# ProProject___2024-04-14.net
KiCad netlist of a schematic drawn in EasyEDA Pro
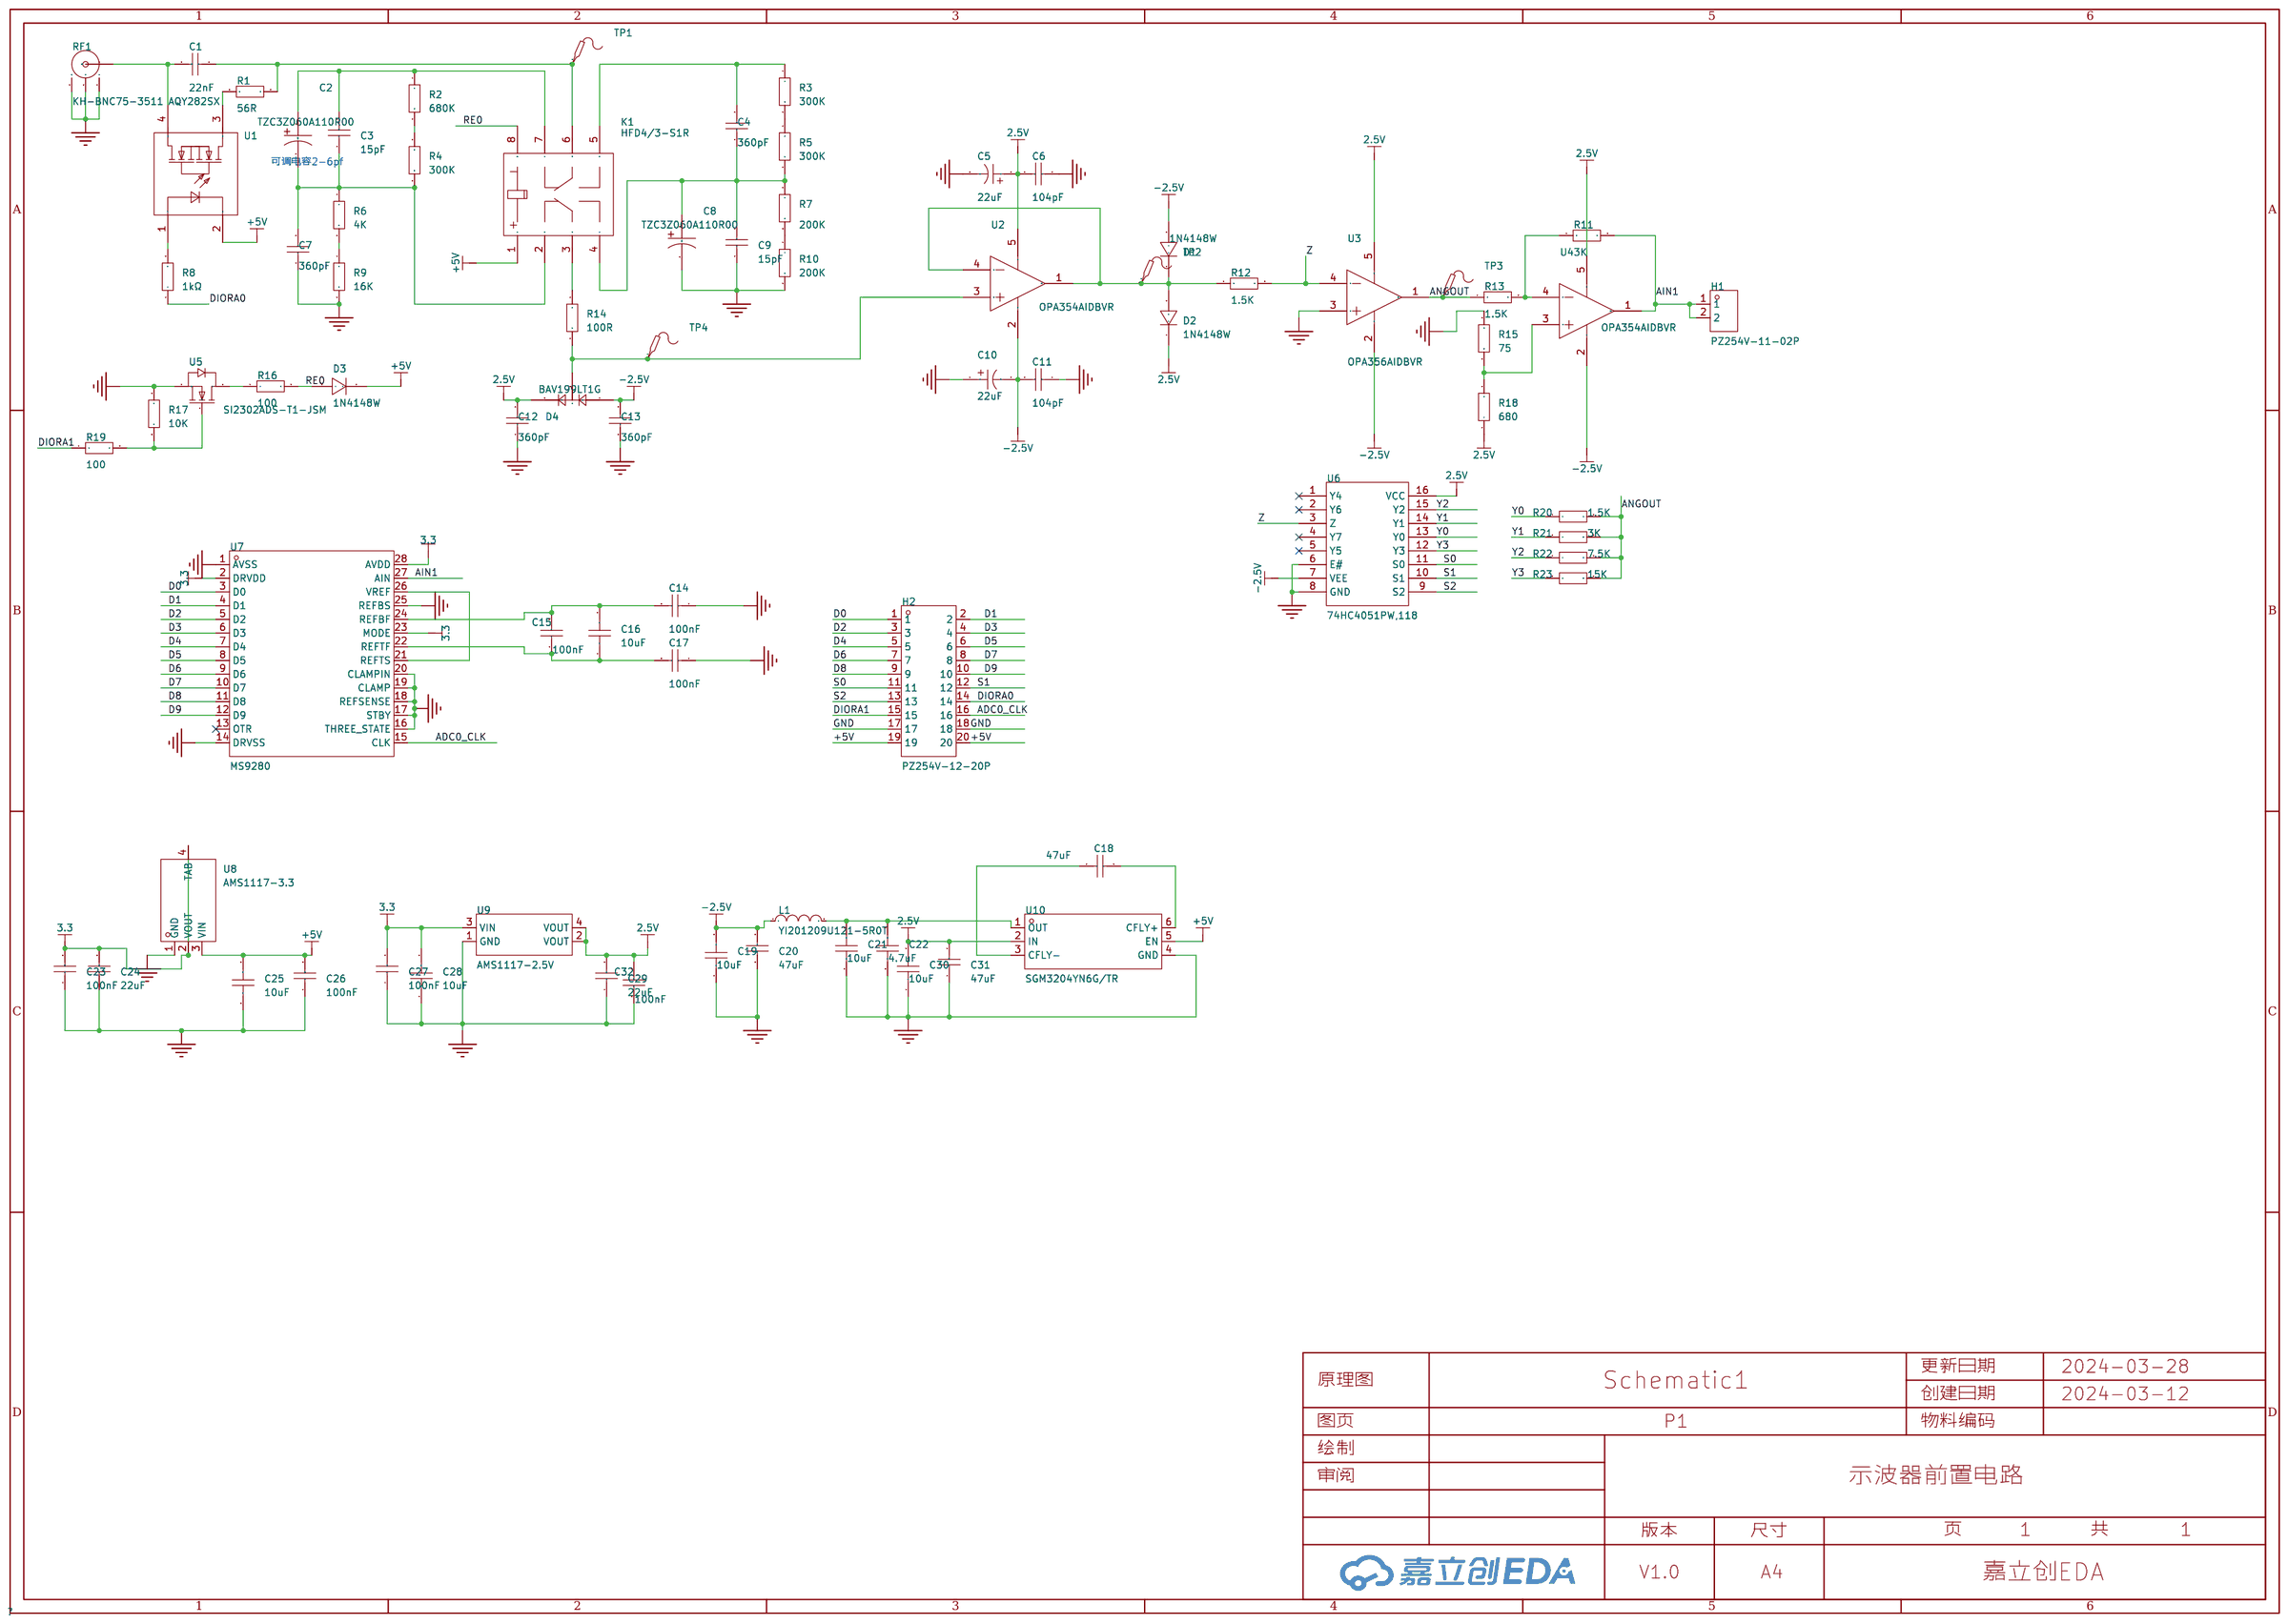
[diagram p0: schematic sheet]

(export (version "E")
  (design (tool "Eeschema 10.0.6"))
  (components
    (comp (ref "C1")
      (value "22nF")
      (footprint "easyedapro:C1206")
      (description "容值:22nF;精度:±5%;额定电压:50V;材质(温度系数):C0G;")
      (fields
        (field (name "Manufacturer Part") "GRM3195C1H223JA01D")
        (field (name "Manufacturer") "muRata(村田)")
      )
      (libsource (lib "easyedapro") (part "GRM3195C1H223JA01D"))
    )
    (comp (ref "C2")
      (value "TZC3Z060A110R00")
      (footprint "easyedapro:CAP-SMD_L4.50-W3.20")
      (description "静电容量:2pF~6pF;静电容量公差:0%~+50%;额定电压(Vdc):100V;Q值:500@1MHz;")
      (fields (field (name "Manufacturer") "muRata(村田)"))
      (libsource (lib "easyedapro") (part "TZC3Z060A110R00"))
    )
    (comp (ref "C3")
      (value "15pF")
      (footprint "easyedapro:C0805")
      (description "容值:1uF;精度:±10%;额定电压:50V;材质(温度系数):X7R;")
      (fields
        (field (name "Manufacturer Part") "CL21B105KBFNNNE")
        (field (name "Manufacturer") "SAMSUNG(三星)")
      )
      (libsource (lib "easyedapro") (part "CL21B105KBFNNNE"))
    )
    (comp (ref "C4")
      (value "360pF")
      (footprint "easyedapro:C0805")
      (description "容值:1uF;精度:±10%;额定电压:50V;材质(温度系数):X7R;")
      (fields
        (field (name "Manufacturer Part") "CL21B105KBFNNNE")
        (field (name "Manufacturer") "SAMSUNG(三星)")
      )
      (libsource (lib "easyedapro") (part "CL21B105KBFNNNE"))
    )
    (comp (ref "C5")
      (value "22uF")
      (footprint "easyedapro:CAP-SMD_BD4.0-L4.3-W4.3-FD-A")
      (description "容值:22uF;精度:±20%;额定电压:16V;纹波电流:21mA@120Hz;等效串联电阻:-;")
      (fields
        (field (name "Manufacturer Part") "RVT22UF16V67RV0017")
        (field (name "Manufacturer") "KNSCHA(科尼盛)")
      )
      (libsource (lib "easyedapro") (part "RVT22UF16V67RV0017"))
    )
    (comp (ref "C6")
      (value "104pF")
      (footprint "easyedapro:C0805")
      (description "容值:1uF;精度:±10%;额定电压:50V;材质(温度系数):X7R;")
      (fields
        (field (name "Manufacturer Part") "CL21B105KBFNNNE")
        (field (name "Manufacturer") "SAMSUNG(三星)")
      )
      (libsource (lib "easyedapro") (part "CL21B105KBFNNNE"))
    )
    (comp (ref "C7")
      (value "360pF")
      (footprint "easyedapro:C0805")
      (description "容值:1uF;精度:±10%;额定电压:50V;材质(温度系数):X7R;")
      (fields
        (field (name "Manufacturer Part") "CL21B105KBFNNNE")
        (field (name "Manufacturer") "SAMSUNG(三星)")
      )
      (libsource (lib "easyedapro") (part "CL21B105KBFNNNE"))
    )
    (comp (ref "C8")
      (value "TZC3Z060A110R00")
      (footprint "easyedapro:CAP-SMD_L4.50-W3.20")
      (description "静电容量:2pF~6pF;静电容量公差:0%~+50%;额定电压(Vdc):100V;Q值:500@1MHz;")
      (fields (field (name "Manufacturer") "muRata(村田)"))
      (libsource (lib "easyedapro") (part "TZC3Z060A110R00"))
    )
    (comp (ref "C9")
      (value "15pF")
      (footprint "easyedapro:C0805")
      (description "容值:1uF;精度:±10%;额定电压:50V;材质(温度系数):X7R;")
      (fields
        (field (name "Manufacturer Part") "CL21B105KBFNNNE")
        (field (name "Manufacturer") "SAMSUNG(三星)")
      )
      (libsource (lib "easyedapro") (part "CL21B105KBFNNNE"))
    )
    (comp (ref "C10")
      (value "22uF")
      (footprint "easyedapro:CAP-SMD_BD4.0-L4.3-W4.3-FD-A")
      (description "容值:22uF;精度:±20%;额定电压:16V;纹波电流:21mA@120Hz;等效串联电阻:-;")
      (fields
        (field (name "Manufacturer Part") "RVT22UF16V67RV0017")
        (field (name "Manufacturer") "KNSCHA(科尼盛)")
      )
      (libsource (lib "easyedapro") (part "RVT22UF16V67RV0017"))
    )
    (comp (ref "C11")
      (value "104pF")
      (footprint "easyedapro:C0805")
      (description "容值:1uF;精度:±10%;额定电压:50V;材质(温度系数):X7R;")
      (fields
        (field (name "Manufacturer Part") "CL21B105KBFNNNE")
        (field (name "Manufacturer") "SAMSUNG(三星)")
      )
      (libsource (lib "easyedapro") (part "CL21B105KBFNNNE"))
    )
    (comp (ref "C12")
      (value "360pF")
      (footprint "easyedapro:C0805")
      (description "容值:1uF;精度:±10%;额定电压:50V;材质(温度系数):X7R;")
      (fields
        (field (name "Manufacturer Part") "CL21B105KBFNNNE")
        (field (name "Manufacturer") "SAMSUNG(三星)")
      )
      (libsource (lib "easyedapro") (part "CL21B105KBFNNNE"))
    )
    (comp (ref "C13")
      (value "360pF")
      (footprint "easyedapro:C0805")
      (description "容值:1uF;精度:±10%;额定电压:50V;材质(温度系数):X7R;")
      (fields
        (field (name "Manufacturer Part") "CL21B105KBFNNNE")
        (field (name "Manufacturer") "SAMSUNG(三星)")
      )
      (libsource (lib "easyedapro") (part "CL21B105KBFNNNE"))
    )
    (comp (ref "C14")
      (value "100nF")
      (footprint "easyedapro:C0805")
      (description "容值:100nF;精度:±10%;额定电压:50V;材质(温度系数):X7R;")
      (fields (field (name "Manufacturer Part") "0805B104K500NT") (field (name "Manufacturer") "FH(风华)"))
      (libsource (lib "easyedapro") (part "0805B104K500NT"))
    )
    (comp (ref "C15")
      (value "100nF")
      (footprint "easyedapro:C0805")
      (description "容值:100nF;精度:±10%;额定电压:50V;材质(温度系数):X7R;")
      (fields (field (name "Manufacturer Part") "0805B104K500NT") (field (name "Manufacturer") "FH(风华)"))
      (libsource (lib "easyedapro") (part "0805B104K500NT"))
    )
    (comp (ref "C16")
      (value "10uF")
      (footprint "easyedapro:C0805")
      (description "容值:10uF;精度:±10%;额定电压:25V;材质(温度系数):X5R;")
      (fields
        (field (name "Manufacturer Part") "CL21A106KAYNNNE")
        (field (name "Manufacturer") "SAMSUNG(三星)")
      )
      (libsource (lib "easyedapro") (part "CL21A106KAYNNNE"))
    )
    (comp (ref "C17")
      (value "100nF")
      (footprint "easyedapro:C0805")
      (description "容值:100nF;精度:±10%;额定电压:50V;材质(温度系数):X7R;")
      (fields (field (name "Manufacturer Part") "0805B104K500NT") (field (name "Manufacturer") "FH(风华)"))
      (libsource (lib "easyedapro") (part "0805B104K500NT"))
    )
    (comp (ref "C18")
      (value "47uF")
      (footprint "easyedapro:C0805")
      (description "容值:100nF;精度:±10%;额定电压:50V;材质(温度系数):X7R;")
      (fields (field (name "Manufacturer Part") "0805B104K500NT") (field (name "Manufacturer") "FH(风华)"))
      (libsource (lib "easyedapro") (part "0805B104K500NT"))
    )
    (comp (ref "C19")
      (value "10uF")
      (footprint "easyedapro:C0805")
      (description "容值:10uF;精度:±10%;额定电压:25V;材质(温度系数):X5R;")
      (fields
        (field (name "Manufacturer Part") "CL21A106KAYNNNE")
        (field (name "Manufacturer") "SAMSUNG(三星)")
      )
      (libsource (lib "easyedapro") (part "CL21A106KAYNNNE"))
    )
    (comp (ref "C20")
      (value "47uF")
      (footprint "easyedapro:C0805")
      (description "容值:100nF;精度:±10%;额定电压:50V;材质(温度系数):X7R;")
      (fields (field (name "Manufacturer Part") "0805B104K500NT") (field (name "Manufacturer") "FH(风华)"))
      (libsource (lib "easyedapro") (part "0805B104K500NT"))
    )
    (comp (ref "C21")
      (value "10uF")
      (footprint "easyedapro:C0805")
      (description "容值:10uF;精度:±10%;额定电压:25V;材质(温度系数):X5R;")
      (fields
        (field (name "Manufacturer Part") "CL21A106KAYNNNE")
        (field (name "Manufacturer") "SAMSUNG(三星)")
      )
      (libsource (lib "easyedapro") (part "CL21A106KAYNNNE"))
    )
    (comp (ref "C22")
      (value "4.7uF")
      (footprint "easyedapro:C0805")
      (description "容值:10uF;精度:±10%;额定电压:25V;材质(温度系数):X5R;")
      (fields
        (field (name "Manufacturer Part") "CL21A106KAYNNNE")
        (field (name "Manufacturer") "SAMSUNG(三星)")
      )
      (libsource (lib "easyedapro") (part "CL21A106KAYNNNE"))
    )
    (comp (ref "C23")
      (value "100nF")
      (footprint "easyedapro:C0805")
      (description "容值:100nF;精度:±10%;额定电压:50V;材质(温度系数):X7R;")
      (fields (field (name "Manufacturer Part") "0805B104K500NT") (field (name "Manufacturer") "FH(风华)"))
      (libsource (lib "easyedapro") (part "0805B104K500NT"))
    )
    (comp (ref "C24")
      (value "22uF")
      (footprint "easyedapro:C0805")
      (description "容值:100nF;精度:±10%;额定电压:50V;材质(温度系数):X7R;")
      (fields (field (name "Manufacturer Part") "0805B104K500NT") (field (name "Manufacturer") "FH(风华)"))
      (libsource (lib "easyedapro") (part "0805B104K500NT"))
    )
    (comp (ref "C25")
      (value "10uF")
      (footprint "easyedapro:C0805")
      (description "容值:10uF;精度:±10%;额定电压:25V;材质(温度系数):X5R;")
      (fields
        (field (name "Manufacturer Part") "CL21A106KAYNNNE")
        (field (name "Manufacturer") "SAMSUNG(三星)")
      )
      (libsource (lib "easyedapro") (part "CL21A106KAYNNNE"))
    )
    (comp (ref "C26")
      (value "100nF")
      (footprint "easyedapro:C0805")
      (description "容值:100nF;精度:±10%;额定电压:50V;材质(温度系数):X7R;")
      (fields (field (name "Manufacturer Part") "0805B104K500NT") (field (name "Manufacturer") "FH(风华)"))
      (libsource (lib "easyedapro") (part "0805B104K500NT"))
    )
    (comp (ref "C27")
      (value "100nF")
      (footprint "easyedapro:C0805")
      (description "容值:100nF;精度:±10%;额定电压:50V;材质(温度系数):X7R;")
      (fields (field (name "Manufacturer Part") "0805B104K500NT") (field (name "Manufacturer") "FH(风华)"))
      (libsource (lib "easyedapro") (part "0805B104K500NT"))
    )
    (comp (ref "C28")
      (value "10uF")
      (footprint "easyedapro:C0805")
      (description "容值:10uF;精度:±10%;额定电压:25V;材质(温度系数):X5R;")
      (fields
        (field (name "Manufacturer Part") "CL21A106KAYNNNE")
        (field (name "Manufacturer") "SAMSUNG(三星)")
      )
      (libsource (lib "easyedapro") (part "CL21A106KAYNNNE"))
    )
    (comp (ref "C29")
      (value "22uF")
      (footprint "easyedapro:C0805")
      (description "容值:100nF;精度:±10%;额定电压:50V;材质(温度系数):X7R;")
      (fields (field (name "Manufacturer Part") "0805B104K500NT") (field (name "Manufacturer") "FH(风华)"))
      (libsource (lib "easyedapro") (part "0805B104K500NT"))
    )
    (comp (ref "C30")
      (value "10uF")
      (footprint "easyedapro:C0805")
      (description "容值:10uF;精度:±10%;额定电压:25V;材质(温度系数):X5R;")
      (fields
        (field (name "Manufacturer Part") "CL21A106KAYNNNE")
        (field (name "Manufacturer") "SAMSUNG(三星)")
      )
      (libsource (lib "easyedapro") (part "CL21A106KAYNNNE"))
    )
    (comp (ref "C31")
      (value "47uF")
      (footprint "easyedapro:C0805")
      (description "容值:100nF;精度:±10%;额定电压:50V;材质(温度系数):X7R;")
      (fields (field (name "Manufacturer Part") "0805B104K500NT") (field (name "Manufacturer") "FH(风华)"))
      (libsource (lib "easyedapro") (part "0805B104K500NT"))
    )
    (comp (ref "C32")
      (value "100nF")
      (footprint "easyedapro:C0805")
      (description "容值:100nF;精度:±10%;额定电压:50V;材质(温度系数):X7R;")
      (fields (field (name "Manufacturer Part") "0805B104K500NT") (field (name "Manufacturer") "FH(风华)"))
      (libsource (lib "easyedapro") (part "0805B104K500NT"))
    )
    (comp (ref "D1")
      (value "1N4148W")
      (footprint "easyedapro:SOD-123_L2.8-W1.8-LS3.7-RD")
      (description "二极管配置:独立式;正向压降(Vf):1.25V@150mA;直流反向耐压(Vr):100V;平均整流电流(Io):150mA;功率:500mW;反向恢复时间(trr):4ns;")
      (fields (field (name "Manufacturer") "CJ(江苏长电/长晶)"))
      (libsource (lib "easyedapro") (part "1N4148W T4"))
    )
    (comp (ref "D2")
      (value "1N4148W")
      (footprint "easyedapro:SOD-123_L2.8-W1.8-LS3.7-RD")
      (description "二极管配置:独立式;正向压降(Vf):1.25V@150mA;直流反向耐压(Vr):100V;平均整流电流(Io):150mA;功率:500mW;反向恢复时间(trr):4ns;")
      (fields (field (name "Manufacturer") "CJ(江苏长电/长晶)"))
      (libsource (lib "easyedapro") (part "1N4148W T4"))
    )
    (comp (ref "D3")
      (value "1N4148W")
      (footprint "easyedapro:SOD-123_L2.8-W1.8-LS3.7-RD")
      (description "二极管配置:独立式;正向压降(Vf):1.25V@150mA;直流反向耐压(Vr):100V;平均整流电流(Io):150mA;功率:500mW;反向恢复时间(trr):4ns;")
      (fields (field (name "Manufacturer") "CJ(江苏长电/长晶)"))
      (libsource (lib "easyedapro") (part "1N4148W T4"))
    )
    (comp (ref "D4")
      (value "BAV199LT1G")
      (footprint "easyedapro:SOT-23_L2.9-W1.3-P1.90-LS2.4-BR")
      (description "二极管配置:1对串联式;正向压降(Vf):1.25V@150mA;直流反向耐压(Vr):70V;平均整流电流(Io):215mA;")
      (fields (field (name "Manufacturer") "onsemi(安森美)"))
      (libsource (lib "easyedapro") (part "BAV199LT1G"))
    )
    (comp (ref "H1")
      (value "PZ254V-11-02P")
      (footprint "easyedapro:HDR-TH_2P-P2.54-V-M")
      (fields (field (name "Manufacturer") "XFCN(兴飞)"))
      (libsource (lib "easyedapro") (part "PZ254V-11-02P"))
    )
    (comp (ref "H2")
      (value "PZ254V-12-20P")
      (footprint "easyedapro:HDR-TH_20P-P2.54-V-M-R2-C10-S2.54")
      (fields (field (name "Manufacturer") "XFCN(兴飞)"))
      (libsource (lib "easyedapro") (part "PZ254V-12-20P"))
    )
    (comp (ref "K1")
      (value "HFD4/3-S1R")
      (footprint "easyedapro:RELAY-SMD_HFD4-3-S1R")
      (description "线圈电压:3V;触点形式:两组转换:2C(双刀双掷-转换);触点容量(电阻负载):1A@30VDC；300mA@125VAC;最大切换电压:250V@AC；220V@DC;最大切换电流:2A;")
      (fields (field (name "Manufacturer") "HF(宏发)"))
      (libsource (lib "easyedapro") (part "HFD4/3-S1R"))
    )
    (comp (ref "L1")
      (value "YI201209U121-5R0T")
      (footprint "easyedapro:L0805")
      (description "标称阻抗@测试频率:120Ω@100MHz;误差:±25%;直流电阻(RDC):30mΩ;")
      (fields (field (name "Manufacturer") "YJYCOIN(益嘉源)"))
      (libsource (lib "easyedapro") (part "YI201209U121-5R0T"))
    )
    (comp (ref "R1")
      (value "56R")
      (footprint "easyedapro:R0805")
      (description "电阻类型:厚膜电阻;阻值:1kΩ;精度:±1%;功率:125mW;最大工作电压:150V;温度系数:±100ppm/°C;")
      (fields
        (field (name "Manufacturer Part") "0805W8F1001T5E")
        (field (name "Manufacturer") "UNI-ROYAL(厚声)")
      )
      (libsource (lib "easyedapro") (part "0805W8F1001T5E"))
    )
    (comp (ref "R2")
      (value "680K")
      (footprint "easyedapro:R0805")
      (description "电阻类型:厚膜电阻;阻值:1kΩ;精度:±1%;功率:125mW;最大工作电压:150V;温度系数:±100ppm/°C;")
      (fields
        (field (name "Manufacturer Part") "0805W8F1001T5E")
        (field (name "Manufacturer") "UNI-ROYAL(厚声)")
      )
      (libsource (lib "easyedapro") (part "0805W8F1001T5E"))
    )
    (comp (ref "R3")
      (value "47K")
      (footprint "easyedapro:R0805")
      (description "电阻类型:厚膜电阻;阻值:1kΩ;精度:±1%;功率:125mW;最大工作电压:150V;温度系数:±100ppm/°C;")
      (fields
        (field (name "Manufacturer Part") "0805W8F1001T5E")
        (field (name "Manufacturer") "UNI-ROYAL(厚声)")
      )
      (libsource (lib "easyedapro") (part "0805W8F1001T5E"))
    )
    (comp (ref "R4")
      (value "300K")
      (footprint "easyedapro:R0805")
      (description "电阻类型:厚膜电阻;阻值:1kΩ;精度:±1%;功率:125mW;最大工作电压:150V;温度系数:±100ppm/°C;")
      (fields
        (field (name "Manufacturer Part") "0805W8F1001T5E")
        (field (name "Manufacturer") "UNI-ROYAL(厚声)")
      )
      (libsource (lib "easyedapro") (part "0805W8F1001T5E"))
    )
    (comp (ref "R5")
      (value "300K")
      (footprint "easyedapro:R0805")
      (description "电阻类型:厚膜电阻;阻值:1kΩ;精度:±1%;功率:125mW;最大工作电压:150V;温度系数:±100ppm/°C;")
      (fields
        (field (name "Manufacturer Part") "0805W8F1001T5E")
        (field (name "Manufacturer") "UNI-ROYAL(厚声)")
      )
      (libsource (lib "easyedapro") (part "0805W8F1001T5E"))
    )
    (comp (ref "R6")
      (value "47K")
      (footprint "easyedapro:R0805")
      (description "电阻类型:厚膜电阻;阻值:1kΩ;精度:±1%;功率:125mW;最大工作电压:150V;温度系数:±100ppm/°C;")
      (fields
        (field (name "Manufacturer Part") "0805W8F1001T5E")
        (field (name "Manufacturer") "UNI-ROYAL(厚声)")
      )
      (libsource (lib "easyedapro") (part "0805W8F1001T5E"))
    )
    (comp (ref "R7")
      (value "200K")
      (footprint "easyedapro:R0805")
      (description "电阻类型:厚膜电阻;阻值:1kΩ;精度:±1%;功率:125mW;最大工作电压:150V;温度系数:±100ppm/°C;")
      (fields
        (field (name "Manufacturer Part") "0805W8F1001T5E")
        (field (name "Manufacturer") "UNI-ROYAL(厚声)")
      )
      (libsource (lib "easyedapro") (part "0805W8F1001T5E"))
    )
    (comp (ref "R8")
      (value "1kΩ")
      (footprint "easyedapro:R0805")
      (description "电阻类型:厚膜电阻;阻值:1kΩ;精度:±1%;功率:125mW;最大工作电压:150V;温度系数:±100ppm/°C;")
      (fields
        (field (name "Manufacturer Part") "0805W8F1001T5E")
        (field (name "Manufacturer") "UNI-ROYAL(厚声)")
      )
      (libsource (lib "easyedapro") (part "0805W8F1001T5E"))
    )
    (comp (ref "R9")
      (value "47K")
      (footprint "easyedapro:R0805")
      (description "电阻类型:厚膜电阻;阻值:1kΩ;精度:±1%;功率:125mW;最大工作电压:150V;温度系数:±100ppm/°C;")
      (fields
        (field (name "Manufacturer Part") "0805W8F1001T5E")
        (field (name "Manufacturer") "UNI-ROYAL(厚声)")
      )
      (libsource (lib "easyedapro") (part "0805W8F1001T5E"))
    )
    (comp (ref "R10")
      (value "200K")
      (footprint "easyedapro:R0805")
      (description "电阻类型:厚膜电阻;阻值:1kΩ;精度:±1%;功率:125mW;最大工作电压:150V;温度系数:±100ppm/°C;")
      (fields
        (field (name "Manufacturer Part") "0805W8F1001T5E")
        (field (name "Manufacturer") "UNI-ROYAL(厚声)")
      )
      (libsource (lib "easyedapro") (part "0805W8F1001T5E"))
    )
    (comp (ref "R11")
      (value "3K")
      (footprint "easyedapro:R0805")
      (description "电阻类型:厚膜电阻;阻值:1kΩ;精度:±1%;功率:125mW;最大工作电压:150V;温度系数:±100ppm/°C;")
      (fields
        (field (name "Manufacturer Part") "0805W8F1001T5E")
        (field (name "Manufacturer") "UNI-ROYAL(厚声)")
      )
      (libsource (lib "easyedapro") (part "0805W8F1001T5E"))
    )
    (comp (ref "R12")
      (value "1.5K")
      (footprint "easyedapro:R0805")
      (description "电阻类型:厚膜电阻;阻值:1kΩ;精度:±1%;功率:125mW;最大工作电压:150V;温度系数:±100ppm/°C;")
      (fields
        (field (name "Manufacturer Part") "0805W8F1001T5E")
        (field (name "Manufacturer") "UNI-ROYAL(厚声)")
      )
      (libsource (lib "easyedapro") (part "0805W8F1001T5E"))
    )
    (comp (ref "R13")
      (value "1.5K")
      (footprint "easyedapro:R0805")
      (description "电阻类型:厚膜电阻;阻值:1kΩ;精度:±1%;功率:125mW;最大工作电压:150V;温度系数:±100ppm/°C;")
      (fields
        (field (name "Manufacturer Part") "0805W8F1001T5E")
        (field (name "Manufacturer") "UNI-ROYAL(厚声)")
      )
      (libsource (lib "easyedapro") (part "0805W8F1001T5E"))
    )
    (comp (ref "R14")
      (value "100R")
      (footprint "easyedapro:R0805")
      (description "电阻类型:厚膜电阻;阻值:1kΩ;精度:±1%;功率:125mW;最大工作电压:150V;温度系数:±100ppm/°C;")
      (fields
        (field (name "Manufacturer Part") "0805W8F1001T5E")
        (field (name "Manufacturer") "UNI-ROYAL(厚声)")
      )
      (libsource (lib "easyedapro") (part "0805W8F1001T5E"))
    )
    (comp (ref "R15")
      (value "75")
      (footprint "easyedapro:R0805")
      (description "电阻类型:厚膜电阻;阻值:1kΩ;精度:±1%;功率:125mW;最大工作电压:150V;温度系数:±100ppm/°C;")
      (fields
        (field (name "Manufacturer Part") "0805W8F1001T5E")
        (field (name "Manufacturer") "UNI-ROYAL(厚声)")
      )
      (libsource (lib "easyedapro") (part "0805W8F1001T5E"))
    )
    (comp (ref "R16")
      (value "47K")
      (footprint "easyedapro:R0805")
      (description "电阻类型:厚膜电阻;阻值:1kΩ;精度:±1%;功率:125mW;最大工作电压:150V;温度系数:±100ppm/°C;")
      (fields
        (field (name "Manufacturer Part") "0805W8F1001T5E")
        (field (name "Manufacturer") "UNI-ROYAL(厚声)")
      )
      (libsource (lib "easyedapro") (part "0805W8F1001T5E"))
    )
    (comp (ref "R17")
      (value "47K")
      (footprint "easyedapro:R0805")
      (description "电阻类型:厚膜电阻;阻值:1kΩ;精度:±1%;功率:125mW;最大工作电压:150V;温度系数:±100ppm/°C;")
      (fields
        (field (name "Manufacturer Part") "0805W8F1001T5E")
        (field (name "Manufacturer") "UNI-ROYAL(厚声)")
      )
      (libsource (lib "easyedapro") (part "0805W8F1001T5E"))
    )
    (comp (ref "R18")
      (value "680")
      (footprint "easyedapro:R0805")
      (description "电阻类型:厚膜电阻;阻值:1kΩ;精度:±1%;功率:125mW;最大工作电压:150V;温度系数:±100ppm/°C;")
      (fields
        (field (name "Manufacturer Part") "0805W8F1001T5E")
        (field (name "Manufacturer") "UNI-ROYAL(厚声)")
      )
      (libsource (lib "easyedapro") (part "0805W8F1001T5E"))
    )
    (comp (ref "R19")
      (value "47K")
      (footprint "easyedapro:R0805")
      (description "电阻类型:厚膜电阻;阻值:1kΩ;精度:±1%;功率:125mW;最大工作电压:150V;温度系数:±100ppm/°C;")
      (fields
        (field (name "Manufacturer Part") "0805W8F1001T5E")
        (field (name "Manufacturer") "UNI-ROYAL(厚声)")
      )
      (libsource (lib "easyedapro") (part "0805W8F1001T5E"))
    )
    (comp (ref "R20")
      (value "1.5K")
      (footprint "easyedapro:R0805")
      (description "电阻类型:厚膜电阻;阻值:1kΩ;精度:±1%;功率:125mW;最大工作电压:150V;温度系数:±100ppm/°C;")
      (fields
        (field (name "Manufacturer Part") "0805W8F1001T5E")
        (field (name "Manufacturer") "UNI-ROYAL(厚声)")
      )
      (libsource (lib "easyedapro") (part "0805W8F1001T5E"))
    )
    (comp (ref "R21")
      (value "3K")
      (footprint "easyedapro:R0805")
      (description "电阻类型:厚膜电阻;阻值:1kΩ;精度:±1%;功率:125mW;最大工作电压:150V;温度系数:±100ppm/°C;")
      (fields
        (field (name "Manufacturer Part") "0805W8F1001T5E")
        (field (name "Manufacturer") "UNI-ROYAL(厚声)")
      )
      (libsource (lib "easyedapro") (part "0805W8F1001T5E"))
    )
    (comp (ref "R22")
      (value "7.5K")
      (footprint "easyedapro:R0805")
      (description "电阻类型:厚膜电阻;阻值:1kΩ;精度:±1%;功率:125mW;最大工作电压:150V;温度系数:±100ppm/°C;")
      (fields
        (field (name "Manufacturer Part") "0805W8F1001T5E")
        (field (name "Manufacturer") "UNI-ROYAL(厚声)")
      )
      (libsource (lib "easyedapro") (part "0805W8F1001T5E"))
    )
    (comp (ref "R23")
      (value "15K")
      (footprint "easyedapro:R0805")
      (description "电阻类型:厚膜电阻;阻值:1kΩ;精度:±1%;功率:125mW;最大工作电压:150V;温度系数:±100ppm/°C;")
      (fields
        (field (name "Manufacturer Part") "0805W8F1001T5E")
        (field (name "Manufacturer") "UNI-ROYAL(厚声)")
      )
      (libsource (lib "easyedapro") (part "0805W8F1001T5E"))
    )
    (comp (ref "RF1")
      (value "KH-BNC75-3511")
      (footprint "easyedapro:ANT-TH_KH-BNC75-3511")
      (fields (field (name "Manufacturer") "kinghelm(金航标)"))
      (libsource (lib "easyedapro") (part "KH-BNC75-3511"))
    )
    (comp (ref "TP1")
      (value "~")
      (footprint "easyedapro:Test-Point-0.5mm")
      (description "Test Point 测试点")
      (libsource (lib "easyedapro") (part "Test-Point"))
    )
    (comp (ref "TP2")
      (value "~")
      (footprint "easyedapro:Test-Point-0.5mm")
      (description "Test Point 测试点")
      (libsource (lib "easyedapro") (part "Test-Point"))
    )
    (comp (ref "TP3")
      (value "~")
      (footprint "easyedapro:Test-Point-0.5mm")
      (description "Test Point 测试点")
      (libsource (lib "easyedapro") (part "Test-Point"))
    )
    (comp (ref "TP4")
      (value "~")
      (footprint "easyedapro:Test-Point-0.5mm")
      (description "Test Point 测试点")
      (libsource (lib "easyedapro") (part "Test-Point"))
    )
    (comp (ref "U1")
      (value "AQY282SX")
      (footprint "easyedapro:SOP-4_L4.3-W4.4-P2.54-LS7.0-BL")
      (description "继电器触点形式:1 Form A(SPST-NO);适用负载类型:AC,DC;正向压降:1.14V;负载电压:60V;连续负载电流:500mA;导通电阻:850mΩ;")
      (fields (field (name "Manufacturer") "PANASONIC(松下)"))
      (libsource (lib "easyedapro") (part "AQY282SX"))
    )
    (comp (ref "U2")
      (value "OPA354AIDBVR")
      (footprint "easyedapro:SOT-23-5_L3.0-W1.7-P0.95-LS2.8-BR")
      (description "放大器数:单路;增益带宽积(GBP):100MHz;输入偏置电流(Ib):3pA;输入失调电压(Vos):2mV;压摆率(SR):150V/us;带宽(-3db):250MHz;轨到轨:-;")
      (fields (field (name "Manufacturer") "TI(德州仪器)"))
      (libsource (lib "easyedapro") (part "OPA354AIDBVR"))
    )
    (comp (ref "U3")
      (value "OPA356AIDBVR")
      (footprint "easyedapro:SOT-23-5_L3.0-W1.7-P0.95-LS2.8-BR")
      (description "放大器数:单路;增益带宽积(GBP):200MHz;输入偏置电流(Ib):3pA;压摆率(SR):360V/us;带宽(-3db):450MHz;轨到轨:-;")
      (fields (field (name "Manufacturer") "TI(德州仪器)"))
      (libsource (lib "easyedapro") (part "OPA356AIDBVR"))
    )
    (comp (ref "U4")
      (value "OPA354AIDBVR")
      (footprint "easyedapro:SOT-23-5_L3.0-W1.7-P0.95-LS2.8-BR")
      (description "放大器数:单路;增益带宽积(GBP):100MHz;输入偏置电流(Ib):3pA;输入失调电压(Vos):2mV;压摆率(SR):150V/us;带宽(-3db):250MHz;轨到轨:-;")
      (fields (field (name "Manufacturer") "TI(德州仪器)"))
      (libsource (lib "easyedapro") (part "OPA354AIDBVR"))
    )
    (comp (ref "U5")
      (value "SI2302ADS-T1-JSM")
      (footprint "easyedapro:SOT-23-3_L2.9-W1.3-P1.90-LS2.4-BR")
      (fields (field (name "Manufacturer") "JSMSEMI(杰盛微)"))
      (libsource (lib "easyedapro") (part "SI2302ADS-T1-JSM"))
    )
    (comp (ref "U6")
      (value "74HC4051PW,118")
      (footprint "easyedapro:TSSOP-16_L5.0-W4.4-P0.65-LS6.4-BL")
      (description "通道数:1;导通电阻(Ron@VCC):120Ω;")
      (fields (field (name "Manufacturer") "Nexperia(安世)"))
      (libsource (lib "easyedapro") (part "74HC4051PW,118"))
    )
    (comp (ref "U7")
      (value "MS9280")
      (footprint "easyedapro:SSOP-28_L10.2-W5.3-P0.65-LS7.8-BL")
      (description "接口:并行;电源电压:2.7V~5.5V;采样率:35MHz;分辨率:10位;")
      (fields (field (name "Manufacturer") "杭州瑞盟"))
      (libsource (lib "easyedapro") (part "MS9280"))
    )
    (comp (ref "U8")
      (value "AMS1117-3.3")
      (footprint "easyedapro:SOT-223-3_L6.5-W3.5-P3.05-LS7.0")
      (description "输出类型：固定 输出极性：正 最大输入电压：18V 输出电压：3.3V 输出电流：1A 电源纹波抑制比(PSRR)：60dB@(120Hz)。当前应用较多领域：三端稳压器，机顶盒")
      (fields (field (name "Manufacturer") "TWGMC(台湾迪嘉)"))
      (libsource (lib "easyedapro") (part "AMS1117-3.3_C5250992"))
    )
    (comp (ref "U9")
      (value "AMS1117-2.5V")
      (footprint "easyedapro:SOT-223_L6.5-W3.5-P2.30-LS7.0-BR")
      (description "输出类型:固定;最大输入电压:18V;输出电压:2.5V;最大输出电流:1A;电源纹波抑制比(PSRR):60dB@(120Hz);输出极性:正极;")
      (fields (field (name "Manufacturer") "MSKSEMI(美森科)"))
      (libsource (lib "easyedapro") (part "AMS1117-2.5V"))
    )
    (comp (ref "U10")
      (value "SGM3204YN6G/TR")
      (footprint "easyedapro:SOT-23-6_L2.9-W1.6-P0.95-LS2.8-BR")
      (description "功能类型:-;输入电压:1.4V~5.5V;输出电压:-5.5V~-1.4V;输出电流(最大值):200mA;")
      (fields (field (name "Manufacturer") "SGMICRO(圣邦微)"))
      (libsource (lib "easyedapro") (part "SGM3204YN6G/TR"))
    )
  )
  (nets
    (net (code "1") (name "+5V") (class "Default")
      (node (ref "C25") (pin "2") (pinfunction "2_2") (pintype "unspecified"))
      (node (ref "C26") (pin "2") (pinfunction "2_2") (pintype "input"))
      (node (ref "D3") (pin "1") (pinfunction "K_1") (pintype "unspecified"))
      (node (ref "H2") (pin "19") (pinfunction "19_19") (pintype "unspecified"))
      (node (ref "H2") (pin "20") (pinfunction "20_20") (pintype "unspecified"))
      (node (ref "K1") (pin "1") (pinfunction "1_1") (pintype "input"))
      (node (ref "U1") (pin "2") (pinfunction "2_2") (pintype "unspecified"))
      (node (ref "U10") (pin "5") (pinfunction "EN_5") (pintype "unspecified"))
      (node (ref "U8") (pin "3") (pinfunction "VIN_3") (pintype "unspecified"))
    )
    (net (code "2") (name "-2.5V") (class "Default")
      (node (ref "C10") (pin "2") (pinfunction "2_2") (pintype "input"))
      (node (ref "C11") (pin "2") (pinfunction "2_2") (pintype "input"))
      (node (ref "C13") (pin "2") (pinfunction "2_2") (pintype "input"))
      (node (ref "C19") (pin "2") (pinfunction "2_2") (pintype "unspecified"))
      (node (ref "C20") (pin "2") (pinfunction "2_2") (pintype "input"))
      (node (ref "D1") (pin "2") (pinfunction "A_2") (pintype "unspecified"))
      (node (ref "D4") (pin "1") (pinfunction "A_1") (pintype "unspecified"))
      (node (ref "L1") (pin "1") (pinfunction "1_1") (pintype "unspecified"))
      (node (ref "U2") (pin "2") (pinfunction "V-_2") (pintype "unspecified"))
      (node (ref "U3") (pin "2") (pinfunction "V-_2") (pintype "unspecified"))
      (node (ref "U4") (pin "2") (pinfunction "V-_2") (pintype "unspecified"))
      (node (ref "U6") (pin "7") (pinfunction "VEE_7") (pintype "input"))
    )
    (net (code "3") (name "/ADC0_CLK") (class "Default")
      (node (ref "H2") (pin "16") (pinfunction "16_16") (pintype "unspecified"))
      (node (ref "U7") (pin "15") (pinfunction "CLK_15") (pintype "input"))
    )
    (net (code "4") (name "/AIN1") (class "Default")
      (node (ref "H1") (pin "1") (pinfunction "1_1") (pintype "unspecified"))
      (node (ref "H1") (pin "2") (pinfunction "2_2") (pintype "unspecified"))
      (node (ref "R11") (pin "2") (pinfunction "2_2") (pintype "input"))
      (node (ref "U4") (pin "1") (pinfunction "OUT_1") (pintype "output"))
      (node (ref "U7") (pin "27") (pinfunction "AIN_27") (pintype "input"))
    )
    (net (code "5") (name "/ANGOUT") (class "Default")
      (node (ref "R13") (pin "1") (pinfunction "1_1") (pintype "input"))
      (node (ref "R20") (pin "2") (pinfunction "2_2") (pintype "input"))
      (node (ref "R21") (pin "2") (pinfunction "2_2") (pintype "input"))
      (node (ref "R22") (pin "2") (pinfunction "2_2") (pintype "input"))
      (node (ref "R23") (pin "2") (pinfunction "2_2") (pintype "input"))
      (node (ref "TP3") (pin "1") (pinfunction "1_1") (pintype "input"))
      (node (ref "U3") (pin "1") (pinfunction "OUT_1") (pintype "output"))
    )
    (net (code "6") (name "/D0") (class "Default")
      (node (ref "H2") (pin "1") (pinfunction "1_1") (pintype "unspecified"))
      (node (ref "U7") (pin "3") (pinfunction "D0_3") (pintype "input"))
    )
    (net (code "7") (name "/D1") (class "Default")
      (node (ref "H2") (pin "2") (pinfunction "2_2") (pintype "unspecified"))
      (node (ref "U7") (pin "4") (pinfunction "D1_4") (pintype "input"))
    )
    (net (code "8") (name "/D2") (class "Default")
      (node (ref "H2") (pin "3") (pinfunction "3_3") (pintype "unspecified"))
      (node (ref "U7") (pin "5") (pinfunction "D2_5") (pintype "input"))
    )
    (net (code "9") (name "/D3") (class "Default")
      (node (ref "H2") (pin "4") (pinfunction "4_4") (pintype "unspecified"))
      (node (ref "U7") (pin "6") (pinfunction "D3_6") (pintype "input"))
    )
    (net (code "10") (name "/D4") (class "Default")
      (node (ref "H2") (pin "5") (pinfunction "5_5") (pintype "unspecified"))
      (node (ref "U7") (pin "7") (pinfunction "D4_7") (pintype "input"))
    )
    (net (code "11") (name "/D5") (class "Default")
      (node (ref "H2") (pin "6") (pinfunction "6_6") (pintype "unspecified"))
      (node (ref "U7") (pin "8") (pinfunction "D5_8") (pintype "input"))
    )
    (net (code "12") (name "/D6") (class "Default")
      (node (ref "H2") (pin "7") (pinfunction "7_7") (pintype "unspecified"))
      (node (ref "U7") (pin "9") (pinfunction "D6_9") (pintype "input"))
    )
    (net (code "13") (name "/D7") (class "Default")
      (node (ref "H2") (pin "8") (pinfunction "8_8") (pintype "unspecified"))
      (node (ref "U7") (pin "10") (pinfunction "D7_10") (pintype "input"))
    )
    (net (code "14") (name "/D8") (class "Default")
      (node (ref "H2") (pin "9") (pinfunction "9_9") (pintype "unspecified"))
      (node (ref "U7") (pin "11") (pinfunction "D8_11") (pintype "input"))
    )
    (net (code "15") (name "/D9") (class "Default")
      (node (ref "H2") (pin "10") (pinfunction "10_10") (pintype "unspecified"))
      (node (ref "U7") (pin "12") (pinfunction "D9_12") (pintype "input"))
    )
    (net (code "16") (name "/DIORA0") (class "Default")
      (node (ref "H2") (pin "14") (pinfunction "14_14") (pintype "unspecified"))
      (node (ref "R8") (pin "1") (pinfunction "1_1") (pintype "input"))
    )
    (net (code "17") (name "/DIORA1") (class "Default")
      (node (ref "H2") (pin "15") (pinfunction "15_15") (pintype "unspecified"))
      (node (ref "R19") (pin "1") (pinfunction "1_1") (pintype "input"))
    )
    (net (code "18") (name "/RE0") (class "Default")
      (node (ref "D3") (pin "2") (pinfunction "A_2") (pintype "unspecified"))
      (node (ref "K1") (pin "8") (pinfunction "8_8") (pintype "input"))
      (node (ref "R16") (pin "2") (pinfunction "2_2") (pintype "input"))
    )
    (net (code "19") (name "/S0") (class "Default")
      (node (ref "H2") (pin "11") (pinfunction "11_11") (pintype "unspecified"))
      (node (ref "U6") (pin "11") (pinfunction "S0_11") (pintype "input"))
    )
    (net (code "20") (name "/S1") (class "Default")
      (node (ref "H2") (pin "12") (pinfunction "12_12") (pintype "unspecified"))
      (node (ref "U6") (pin "10") (pinfunction "S1_10") (pintype "input"))
    )
    (net (code "21") (name "/S2") (class "Default")
      (node (ref "H2") (pin "13") (pinfunction "13_13") (pintype "unspecified"))
      (node (ref "U6") (pin "9") (pinfunction "S2_9") (pintype "input"))
    )
    (net (code "22") (name "/Y0") (class "Default")
      (node (ref "R20") (pin "1") (pinfunction "1_1") (pintype "input"))
      (node (ref "U6") (pin "13") (pinfunction "Y0_13") (pintype "input"))
    )
    (net (code "23") (name "/Y1") (class "Default")
      (node (ref "R21") (pin "1") (pinfunction "1_1") (pintype "input"))
      (node (ref "U6") (pin "14") (pinfunction "Y1_14") (pintype "input"))
    )
    (net (code "24") (name "/Y2") (class "Default")
      (node (ref "R22") (pin "1") (pinfunction "1_1") (pintype "input"))
      (node (ref "U6") (pin "15") (pinfunction "Y2_15") (pintype "input"))
    )
    (net (code "25") (name "/Y3") (class "Default")
      (node (ref "R23") (pin "1") (pinfunction "1_1") (pintype "input"))
      (node (ref "U6") (pin "12") (pinfunction "Y3_12") (pintype "input"))
    )
    (net (code "26") (name "/Z") (class "Default")
      (node (ref "R12") (pin "2") (pinfunction "2_2") (pintype "input"))
      (node (ref "U3") (pin "4") (pinfunction "IN-_4") (pintype "unspecified"))
      (node (ref "U6") (pin "3") (pinfunction "Z_3") (pintype "input"))
    )
    (net (code "27") (name "2.5V") (class "Default")
      (node (ref "C12") (pin "2") (pinfunction "2_2") (pintype "input"))
      (node (ref "C29") (pin "2") (pinfunction "2_2") (pintype "input"))
      (node (ref "C30") (pin "2") (pinfunction "2_2") (pintype "unspecified"))
      (node (ref "C31") (pin "2") (pinfunction "2_2") (pintype "input"))
      (node (ref "C32") (pin "2") (pinfunction "2_2") (pintype "input"))
      (node (ref "C5") (pin "1") (pinfunction "1_1") (pintype "input"))
      (node (ref "C6") (pin "2") (pinfunction "2_2") (pintype "input"))
      (node (ref "D2") (pin "1") (pinfunction "K_1") (pintype "unspecified"))
      (node (ref "D4") (pin "2") (pinfunction "C_2") (pintype "unspecified"))
      (node (ref "R18") (pin "1") (pinfunction "1_1") (pintype "input"))
      (node (ref "U10") (pin "2") (pinfunction "IN_2") (pintype "unspecified"))
      (node (ref "U2") (pin "5") (pinfunction "V+_5") (pintype "unspecified"))
      (node (ref "U3") (pin "5") (pinfunction "V+_5") (pintype "unspecified"))
      (node (ref "U4") (pin "5") (pinfunction "V+_5") (pintype "unspecified"))
      (node (ref "U6") (pin "16") (pinfunction "VCC_16") (pintype "input"))
      (node (ref "U9") (pin "2") (pinfunction "VOUT_2") (pintype "unspecified"))
      (node (ref "U9") (pin "4") (pinfunction "VOUT_4") (pintype "unspecified"))
    )
    (net (code "28") (name "3.3") (class "Default")
      (node (ref "C23") (pin "2") (pinfunction "2_2") (pintype "input"))
      (node (ref "C24") (pin "2") (pinfunction "2_2") (pintype "input"))
      (node (ref "C27") (pin "2") (pinfunction "2_2") (pintype "input"))
      (node (ref "C28") (pin "2") (pinfunction "2_2") (pintype "unspecified"))
      (node (ref "U7") (pin "2") (pinfunction "DRVDD_2") (pintype "input"))
      (node (ref "U7") (pin "23") (pinfunction "MODE_23") (pintype "input"))
      (node (ref "U7") (pin "28") (pinfunction "AVDD_28") (pintype "input"))
      (node (ref "U8") (pin "2") (pinfunction "VOUT_2") (pintype "unspecified"))
      (node (ref "U8") (pin "4") (pinfunction "TAB_4") (pintype "unspecified"))
      (node (ref "U9") (pin "3") (pinfunction "VIN_3") (pintype "unspecified"))
    )
    (net (code "29") (name "GND") (class "Default")
      (node (ref "C10") (pin "1") (pinfunction "1_1") (pintype "input"))
      (node (ref "C11") (pin "1") (pinfunction "1_1") (pintype "input"))
      (node (ref "C12") (pin "1") (pinfunction "1_1") (pintype "input"))
      (node (ref "C13") (pin "1") (pinfunction "1_1") (pintype "input"))
      (node (ref "C14") (pin "1") (pinfunction "1_1") (pintype "input"))
      (node (ref "C17") (pin "1") (pinfunction "1_1") (pintype "input"))
      (node (ref "C19") (pin "1") (pinfunction "1_1") (pintype "unspecified"))
      (node (ref "C20") (pin "1") (pinfunction "1_1") (pintype "input"))
      (node (ref "C21") (pin "1") (pinfunction "1_1") (pintype "unspecified"))
      (node (ref "C22") (pin "1") (pinfunction "1_1") (pintype "unspecified"))
      (node (ref "C23") (pin "1") (pinfunction "1_1") (pintype "input"))
      (node (ref "C24") (pin "1") (pinfunction "1_1") (pintype "input"))
      (node (ref "C25") (pin "1") (pinfunction "1_1") (pintype "unspecified"))
      (node (ref "C26") (pin "1") (pinfunction "1_1") (pintype "input"))
      (node (ref "C27") (pin "1") (pinfunction "1_1") (pintype "input"))
      (node (ref "C28") (pin "1") (pinfunction "1_1") (pintype "unspecified"))
      (node (ref "C29") (pin "1") (pinfunction "1_1") (pintype "input"))
      (node (ref "C30") (pin "1") (pinfunction "1_1") (pintype "unspecified"))
      (node (ref "C31") (pin "1") (pinfunction "1_1") (pintype "input"))
      (node (ref "C32") (pin "1") (pinfunction "1_1") (pintype "input"))
      (node (ref "C5") (pin "2") (pinfunction "2_2") (pintype "input"))
      (node (ref "C6") (pin "1") (pinfunction "1_1") (pintype "input"))
      (node (ref "C7") (pin "1") (pinfunction "1_1") (pintype "input"))
      (node (ref "C8") (pin "2") (pinfunction "2_2") (pintype "unspecified"))
      (node (ref "C9") (pin "1") (pinfunction "1_1") (pintype "input"))
      (node (ref "H2") (pin "17") (pinfunction "17_17") (pintype "unspecified"))
      (node (ref "H2") (pin "18") (pinfunction "18_18") (pintype "unspecified"))
      (node (ref "R10") (pin "2") (pinfunction "2_2") (pintype "input"))
      (node (ref "R15") (pin "2") (pinfunction "2_2") (pintype "input"))
      (node (ref "R17") (pin "1") (pinfunction "1_1") (pintype "input"))
      (node (ref "R9") (pin "2") (pinfunction "2_2") (pintype "input"))
      (node (ref "RF1") (pin "2") (pinfunction "2_2") (pintype "unspecified"))
      (node (ref "RF1") (pin "3") (pinfunction "3_3") (pintype "unspecified"))
      (node (ref "RF1") (pin "4") (pinfunction "4_4") (pintype "unspecified"))
      (node (ref "U10") (pin "4") (pinfunction "GND_4") (pintype "unspecified"))
      (node (ref "U3") (pin "3") (pinfunction "IN+_3") (pintype "unspecified"))
      (node (ref "U5") (pin "2") (pinfunction "S_2") (pintype "unspecified"))
      (node (ref "U6") (pin "6") (pinfunction "E#_6") (pintype "input"))
      (node (ref "U6") (pin "8") (pinfunction "GND_8") (pintype "input"))
      (node (ref "U7") (pin "1") (pinfunction "AVSS_1") (pintype "input"))
      (node (ref "U7") (pin "14") (pinfunction "DRVSS_14") (pintype "input"))
      (node (ref "U7") (pin "16") (pinfunction "THREE_STATE_16") (pintype "input"))
      (node (ref "U7") (pin "17") (pinfunction "STBY_17") (pintype "input"))
      (node (ref "U7") (pin "18") (pinfunction "REFSENSE_18") (pintype "input"))
      (node (ref "U7") (pin "19") (pinfunction "CLAMP_19") (pintype "input"))
      (node (ref "U7") (pin "20") (pinfunction "CLAMPIN_20") (pintype "input"))
      (node (ref "U7") (pin "25") (pinfunction "REFBS_25") (pintype "input"))
      (node (ref "U8") (pin "1") (pinfunction "GND_1") (pintype "unspecified"))
      (node (ref "U9") (pin "1") (pinfunction "GND_1") (pintype "unspecified"))
    )
    (net (code "30") (name "Net-(C1-Pad2)") (class "Default")
      (node (ref "C1") (pin "2") (pinfunction "2_2") (pintype "input"))
      (node (ref "K1") (pin "6") (pinfunction "6_6") (pintype "input"))
      (node (ref "R1") (pin "1") (pinfunction "1_1") (pintype "input"))
      (node (ref "TP1") (pin "1") (pinfunction "1_1") (pintype "input"))
    )
    (net (code "31") (name "Net-(C2-Pad1)") (class "Default")
      (node (ref "C2") (pin "1") (pinfunction "1_1") (pintype "unspecified"))
      (node (ref "C3") (pin "2") (pinfunction "2_2") (pintype "input"))
      (node (ref "K1") (pin "7") (pinfunction "7_7") (pintype "input"))
      (node (ref "R2") (pin "1") (pinfunction "1_1") (pintype "input"))
    )
    (net (code "32") (name "Net-(C2-Pad2)") (class "Default")
      (node (ref "C2") (pin "2") (pinfunction "2_2") (pintype "unspecified"))
      (node (ref "C3") (pin "1") (pinfunction "1_1") (pintype "input"))
      (node (ref "C7") (pin "2") (pinfunction "2_2") (pintype "input"))
      (node (ref "K1") (pin "2") (pinfunction "2_2") (pintype "input"))
      (node (ref "R4") (pin "2") (pinfunction "2_2") (pintype "input"))
      (node (ref "R6") (pin "1") (pinfunction "1_1") (pintype "input"))
    )
    (net (code "33") (name "Net-(C4-Pad1)") (class "Default")
      (node (ref "C4") (pin "1") (pinfunction "1_1") (pintype "input"))
      (node (ref "C8") (pin "1") (pinfunction "1_1") (pintype "unspecified"))
      (node (ref "C9") (pin "2") (pinfunction "2_2") (pintype "input"))
      (node (ref "K1") (pin "4") (pinfunction "4_4") (pintype "input"))
      (node (ref "R5") (pin "2") (pinfunction "2_2") (pintype "input"))
      (node (ref "R7") (pin "1") (pinfunction "1_1") (pintype "input"))
    )
    (net (code "34") (name "Net-(C4-Pad2)") (class "Default")
      (node (ref "C4") (pin "2") (pinfunction "2_2") (pintype "input"))
      (node (ref "K1") (pin "5") (pinfunction "5_5") (pintype "input"))
      (node (ref "R3") (pin "1") (pinfunction "1_1") (pintype "input"))
    )
    (net (code "35") (name "Net-(D1-K)") (class "Default")
      (node (ref "D1") (pin "1") (pinfunction "K_1") (pintype "unspecified"))
      (node (ref "D2") (pin "2") (pinfunction "A_2") (pintype "unspecified"))
      (node (ref "R12") (pin "1") (pinfunction "1_1") (pintype "input"))
      (node (ref "TP2") (pin "1") (pinfunction "1_1") (pintype "input"))
      (node (ref "U2") (pin "1") (pinfunction "OUT_1") (pintype "output"))
      (node (ref "U2") (pin "4") (pinfunction "IN-_4") (pintype "unspecified"))
    )
    (net (code "36") (name "Net-(D4-C{slash}A)") (class "Default")
      (node (ref "D4") (pin "3") (pinfunction "C/A_3") (pintype "unspecified"))
      (node (ref "R14") (pin "2") (pinfunction "2_2") (pintype "input"))
      (node (ref "TP4") (pin "1") (pinfunction "1_1") (pintype "input"))
      (node (ref "U2") (pin "3") (pinfunction "IN+_3") (pintype "unspecified"))
    )
    (net (code "37") (name "Net-(K1-Pad3)") (class "Default")
      (node (ref "K1") (pin "3") (pinfunction "3_3") (pintype "input"))
      (node (ref "R14") (pin "1") (pinfunction "1_1") (pintype "input"))
    )
    (net (code "38") (name "Net-(R1-Pad2)") (class "Default")
      (node (ref "R1") (pin "2") (pinfunction "2_2") (pintype "input"))
      (node (ref "U1") (pin "3") (pinfunction "3_3") (pintype "unspecified"))
    )
    (net (code "39") (name "Net-(R2-Pad2)") (class "Default")
      (node (ref "R2") (pin "2") (pinfunction "2_2") (pintype "input"))
      (node (ref "R4") (pin "1") (pinfunction "1_1") (pintype "input"))
    )
    (net (code "40") (name "Net-(R3-Pad2)") (class "Default")
      (node (ref "R3") (pin "2") (pinfunction "2_2") (pintype "input"))
      (node (ref "R5") (pin "1") (pinfunction "1_1") (pintype "input"))
    )
    (net (code "41") (name "Net-(R6-Pad2)") (class "Default")
      (node (ref "R6") (pin "2") (pinfunction "2_2") (pintype "input"))
      (node (ref "R9") (pin "1") (pinfunction "1_1") (pintype "input"))
    )
    (net (code "42") (name "Net-(R8-Pad2)") (class "Default")
      (node (ref "R8") (pin "2") (pinfunction "2_2") (pintype "input"))
      (node (ref "U1") (pin "1") (pinfunction "1_1") (pintype "unspecified"))
    )
    (net (code "43") (name "Net-(R10-Pad1)") (class "Default")
      (node (ref "R10") (pin "1") (pinfunction "1_1") (pintype "input"))
      (node (ref "R7") (pin "2") (pinfunction "2_2") (pintype "input"))
    )
    (net (code "44") (name "Net-(RF1-OUT)") (class "Default")
      (node (ref "C1") (pin "1") (pinfunction "1_1") (pintype "input"))
      (node (ref "RF1") (pin "1") (pinfunction "OUT_1") (pintype "unspecified"))
      (node (ref "U1") (pin "4") (pinfunction "4_4") (pintype "unspecified"))
    )
    (net (code "45") (name "Net-(U4-IN+)") (class "Default")
      (node (ref "R15") (pin "1") (pinfunction "1_1") (pintype "input"))
      (node (ref "R18") (pin "2") (pinfunction "2_2") (pintype "input"))
      (node (ref "U4") (pin "3") (pinfunction "IN+_3") (pintype "unspecified"))
    )
    (net (code "46") (name "Net-(U4-IN-)") (class "Default")
      (node (ref "R11") (pin "1") (pinfunction "1_1") (pintype "input"))
      (node (ref "R13") (pin "2") (pinfunction "2_2") (pintype "input"))
      (node (ref "U4") (pin "4") (pinfunction "IN-_4") (pintype "unspecified"))
    )
    (net (code "47") (name "Net-(U5-D)") (class "Default")
      (node (ref "R16") (pin "1") (pinfunction "1_1") (pintype "input"))
      (node (ref "U5") (pin "3") (pinfunction "D_3") (pintype "unspecified"))
    )
    (net (code "48") (name "Net-(U5-G)") (class "Default")
      (node (ref "R17") (pin "2") (pinfunction "2_2") (pintype "input"))
      (node (ref "R19") (pin "2") (pinfunction "2_2") (pintype "input"))
      (node (ref "U5") (pin "1") (pinfunction "G_1") (pintype "unspecified"))
    )
    (net (code "49") (name "Net-(U7-REFBF)") (class "Default")
      (node (ref "C14") (pin "2") (pinfunction "2_2") (pintype "input"))
      (node (ref "C15") (pin "2") (pinfunction "2_2") (pintype "input"))
      (node (ref "C16") (pin "2") (pinfunction "2_2") (pintype "unspecified"))
      (node (ref "U7") (pin "24") (pinfunction "REFBF_24") (pintype "input"))
    )
    (net (code "50") (name "Net-(U7-REFTF)") (class "Default")
      (node (ref "C15") (pin "1") (pinfunction "1_1") (pintype "input"))
      (node (ref "C16") (pin "1") (pinfunction "1_1") (pintype "unspecified"))
      (node (ref "C17") (pin "2") (pinfunction "2_2") (pintype "input"))
      (node (ref "U7") (pin "22") (pinfunction "REFTF_22") (pintype "input"))
    )
    (net (code "51") (name "Net-(U7-REFTS)") (class "Default")
      (node (ref "U7") (pin "21") (pinfunction "REFTS_21") (pintype "input"))
      (node (ref "U7") (pin "26") (pinfunction "VREF_26") (pintype "input"))
    )
    (net (code "52") (name "Net-(U10-CFLY+)") (class "Default")
      (node (ref "C18") (pin "1") (pinfunction "1_1") (pintype "input"))
      (node (ref "U10") (pin "6") (pinfunction "CFLY+_6") (pintype "unspecified"))
    )
    (net (code "53") (name "Net-(U10-CFLY-)") (class "Default")
      (node (ref "C18") (pin "2") (pinfunction "2_2") (pintype "input"))
      (node (ref "U10") (pin "3") (pinfunction "CFLY-_3") (pintype "unspecified"))
    )
    (net (code "54") (name "Net-(U10-OUT)") (class "Default")
      (node (ref "C21") (pin "2") (pinfunction "2_2") (pintype "unspecified"))
      (node (ref "C22") (pin "2") (pinfunction "2_2") (pintype "unspecified"))
      (node (ref "L1") (pin "2") (pinfunction "2_2") (pintype "unspecified"))
      (node (ref "U10") (pin "1") (pinfunction "OUT_1") (pintype "unspecified"))
    )
    (net (code "55") (name "unconnected-(U6-Y4-Pad1)") (class "Default")
      (node (ref "U6") (pin "1") (pinfunction "Y4_1") (pintype "input+no_connect"))
    )
    (net (code "56") (name "unconnected-(U6-Y5-Pad5)") (class "Default")
      (node (ref "U6") (pin "5") (pinfunction "Y5_5") (pintype "input+no_connect"))
    )
    (net (code "57") (name "unconnected-(U6-Y6-Pad2)") (class "Default")
      (node (ref "U6") (pin "2") (pinfunction "Y6_2") (pintype "input+no_connect"))
    )
    (net (code "58") (name "unconnected-(U6-Y7-Pad4)") (class "Default")
      (node (ref "U6") (pin "4") (pinfunction "Y7_4") (pintype "input+no_connect"))
    )
    (net (code "59") (name "unconnected-(U7-OTR-Pad13)") (class "Default")
      (node (ref "U7") (pin "13") (pinfunction "OTR_13") (pintype "input+no_connect"))
    )
  )
)
